# USB_BusinessCard.net
KiCad netlist of a schematic drawn in EAGLE
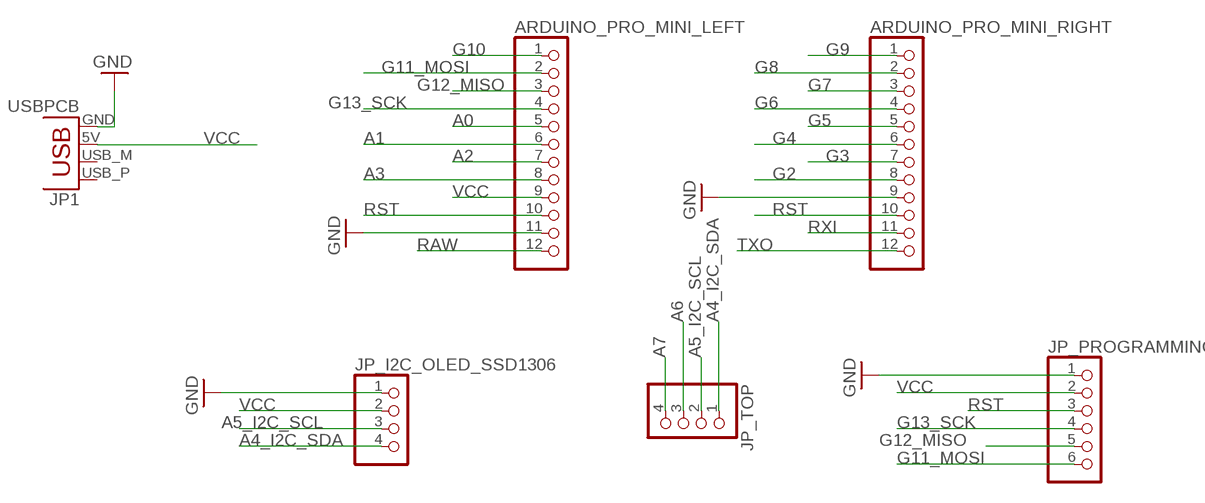
[diagram p0: schematic, sheet 1]

(export (version "E")
  (design (tool "Eeschema 10.0.6"))
  (components
    (comp (ref "ARDUINO_PRO_MINI_LEFT")
      (value "PINHD-1X12")
      (footprint "eagle-import:1X12")
      (libsource (lib "eagle-import") (part "PINHD-1X12"))
    )
    (comp (ref "ARDUINO_PRO_MINI_RIGHT")
      (value "PINHD-1X12")
      (footprint "eagle-import:1X12")
      (libsource (lib "eagle-import") (part "PINHD-1X12"))
    )
    (comp (ref "JP1")
      (value "USBPCB")
      (footprint "eagle-import:USB-A-PCB")
      (libsource (lib "eagle-import") (part "USBPCB"))
    )
    (comp (ref "JP_I2C_OLED_SSD1306")
      (value "PINHD-1X4")
      (footprint "eagle-import:1X04")
      (libsource (lib "eagle-import") (part "PINHD-1X4"))
    )
    (comp (ref "JP_PROGRAMMING")
      (value "PINHD-1X6")
      (footprint "eagle-import:1X06")
      (libsource (lib "eagle-import") (part "PINHD-1X6"))
    )
    (comp (ref "JP_TOP")
      (value "PINHD-1X4")
      (footprint "eagle-import:1X04")
      (libsource (lib "eagle-import") (part "PINHD-1X4"))
    )
  )
  (nets
    (net (code "1") (name "/A0") (class "Default")
      (node (ref "ARDUINO_PRO_MINI_LEFT") (pin "5") (pinfunction "5_5") (pintype "passive"))
    )
    (net (code "2") (name "/A1") (class "Default")
      (node (ref "ARDUINO_PRO_MINI_LEFT") (pin "6") (pinfunction "6_6") (pintype "passive"))
    )
    (net (code "3") (name "/A2") (class "Default")
      (node (ref "ARDUINO_PRO_MINI_LEFT") (pin "7") (pinfunction "7_7") (pintype "passive"))
    )
    (net (code "4") (name "/A3") (class "Default")
      (node (ref "ARDUINO_PRO_MINI_LEFT") (pin "8") (pinfunction "8_8") (pintype "passive"))
    )
    (net (code "5") (name "/A4_I2C_SDA") (class "Default")
      (node (ref "JP_I2C_OLED_SSD1306") (pin "4") (pinfunction "4_4") (pintype "passive"))
      (node (ref "JP_TOP") (pin "1") (pinfunction "1_1") (pintype "passive"))
    )
    (net (code "6") (name "/A5_I2C_SCL") (class "Default")
      (node (ref "JP_I2C_OLED_SSD1306") (pin "3") (pinfunction "3_3") (pintype "passive"))
      (node (ref "JP_TOP") (pin "2") (pinfunction "2_2") (pintype "passive"))
    )
    (net (code "7") (name "/A6") (class "Default")
      (node (ref "JP_TOP") (pin "3") (pinfunction "3_3") (pintype "passive"))
    )
    (net (code "8") (name "/A7") (class "Default")
      (node (ref "JP_TOP") (pin "4") (pinfunction "4_4") (pintype "passive"))
    )
    (net (code "9") (name "/G2") (class "Default")
      (node (ref "ARDUINO_PRO_MINI_RIGHT") (pin "8") (pinfunction "8_8") (pintype "passive"))
    )
    (net (code "10") (name "/G3") (class "Default")
      (node (ref "ARDUINO_PRO_MINI_RIGHT") (pin "7") (pinfunction "7_7") (pintype "passive"))
    )
    (net (code "11") (name "/G4") (class "Default")
      (node (ref "ARDUINO_PRO_MINI_RIGHT") (pin "6") (pinfunction "6_6") (pintype "passive"))
    )
    (net (code "12") (name "/G5") (class "Default")
      (node (ref "ARDUINO_PRO_MINI_RIGHT") (pin "5") (pinfunction "5_5") (pintype "passive"))
    )
    (net (code "13") (name "/G6") (class "Default")
      (node (ref "ARDUINO_PRO_MINI_RIGHT") (pin "4") (pinfunction "4_4") (pintype "passive"))
    )
    (net (code "14") (name "/G7") (class "Default")
      (node (ref "ARDUINO_PRO_MINI_RIGHT") (pin "3") (pinfunction "3_3") (pintype "passive"))
    )
    (net (code "15") (name "/G8") (class "Default")
      (node (ref "ARDUINO_PRO_MINI_RIGHT") (pin "2") (pinfunction "2_2") (pintype "passive"))
    )
    (net (code "16") (name "/G9") (class "Default")
      (node (ref "ARDUINO_PRO_MINI_RIGHT") (pin "1") (pinfunction "1_1") (pintype "passive"))
    )
    (net (code "17") (name "/G10") (class "Default")
      (node (ref "ARDUINO_PRO_MINI_LEFT") (pin "1") (pinfunction "1_1") (pintype "passive"))
    )
    (net (code "18") (name "/G11_MOSI") (class "Default")
      (node (ref "ARDUINO_PRO_MINI_LEFT") (pin "2") (pinfunction "2_2") (pintype "passive"))
      (node (ref "JP_PROGRAMMING") (pin "6") (pinfunction "6_6") (pintype "passive"))
    )
    (net (code "19") (name "/G12_MISO") (class "Default")
      (node (ref "ARDUINO_PRO_MINI_LEFT") (pin "3") (pinfunction "3_3") (pintype "passive"))
      (node (ref "JP_PROGRAMMING") (pin "5") (pinfunction "5_5") (pintype "passive"))
    )
    (net (code "20") (name "/G13_SCK") (class "Default")
      (node (ref "ARDUINO_PRO_MINI_LEFT") (pin "4") (pinfunction "4_4") (pintype "passive"))
      (node (ref "JP_PROGRAMMING") (pin "4") (pinfunction "4_4") (pintype "passive"))
    )
    (net (code "21") (name "/RAW") (class "Default")
      (node (ref "ARDUINO_PRO_MINI_LEFT") (pin "12") (pinfunction "12_12") (pintype "passive"))
    )
    (net (code "22") (name "/RST") (class "Default")
      (node (ref "ARDUINO_PRO_MINI_LEFT") (pin "10") (pinfunction "10_10") (pintype "passive"))
      (node (ref "ARDUINO_PRO_MINI_RIGHT") (pin "10") (pinfunction "10_10") (pintype "passive"))
      (node (ref "JP_PROGRAMMING") (pin "3") (pinfunction "3_3") (pintype "passive"))
    )
    (net (code "23") (name "/RXI") (class "Default")
      (node (ref "ARDUINO_PRO_MINI_RIGHT") (pin "11") (pinfunction "11_11") (pintype "passive"))
    )
    (net (code "24") (name "/TXO") (class "Default")
      (node (ref "ARDUINO_PRO_MINI_RIGHT") (pin "12") (pinfunction "12_12") (pintype "passive"))
    )
    (net (code "25") (name "/VCC") (class "Default")
      (node (ref "ARDUINO_PRO_MINI_LEFT") (pin "9") (pinfunction "9_9") (pintype "passive"))
      (node (ref "JP1") (pin "5V") (pinfunction "VBUS_5V") (pintype "bidirectional"))
      (node (ref "JP_I2C_OLED_SSD1306") (pin "2") (pinfunction "2_2") (pintype "passive"))
      (node (ref "JP_PROGRAMMING") (pin "2") (pinfunction "2_2") (pintype "passive"))
    )
    (net (code "26") (name "GND") (class "Default")
      (node (ref "ARDUINO_PRO_MINI_LEFT") (pin "11") (pinfunction "11_11") (pintype "passive"))
      (node (ref "ARDUINO_PRO_MINI_RIGHT") (pin "9") (pinfunction "9_9") (pintype "passive"))
      (node (ref "JP1") (pin "GND") (pinfunction "GND_GND") (pintype "bidirectional"))
      (node (ref "JP_I2C_OLED_SSD1306") (pin "1") (pinfunction "1_1") (pintype "passive"))
      (node (ref "JP_PROGRAMMING") (pin "1") (pinfunction "1_1") (pintype "passive"))
    )
    (net (code "27") (name "unconnected-(JP1-D+-PadUSB_P)") (class "Default")
      (node (ref "JP1") (pin "USB_P") (pinfunction "D+_USB_P") (pintype "bidirectional"))
    )
    (net (code "28") (name "unconnected-(JP1-D--PadUSB_M)") (class "Default")
      (node (ref "JP1") (pin "USB_M") (pinfunction "D-_USB_M") (pintype "bidirectional"))
    )
  )
)
